# I2C_GPIOs_MIPI-CSI.net
KiCad netlist of a schematic drawn in Altium Designer
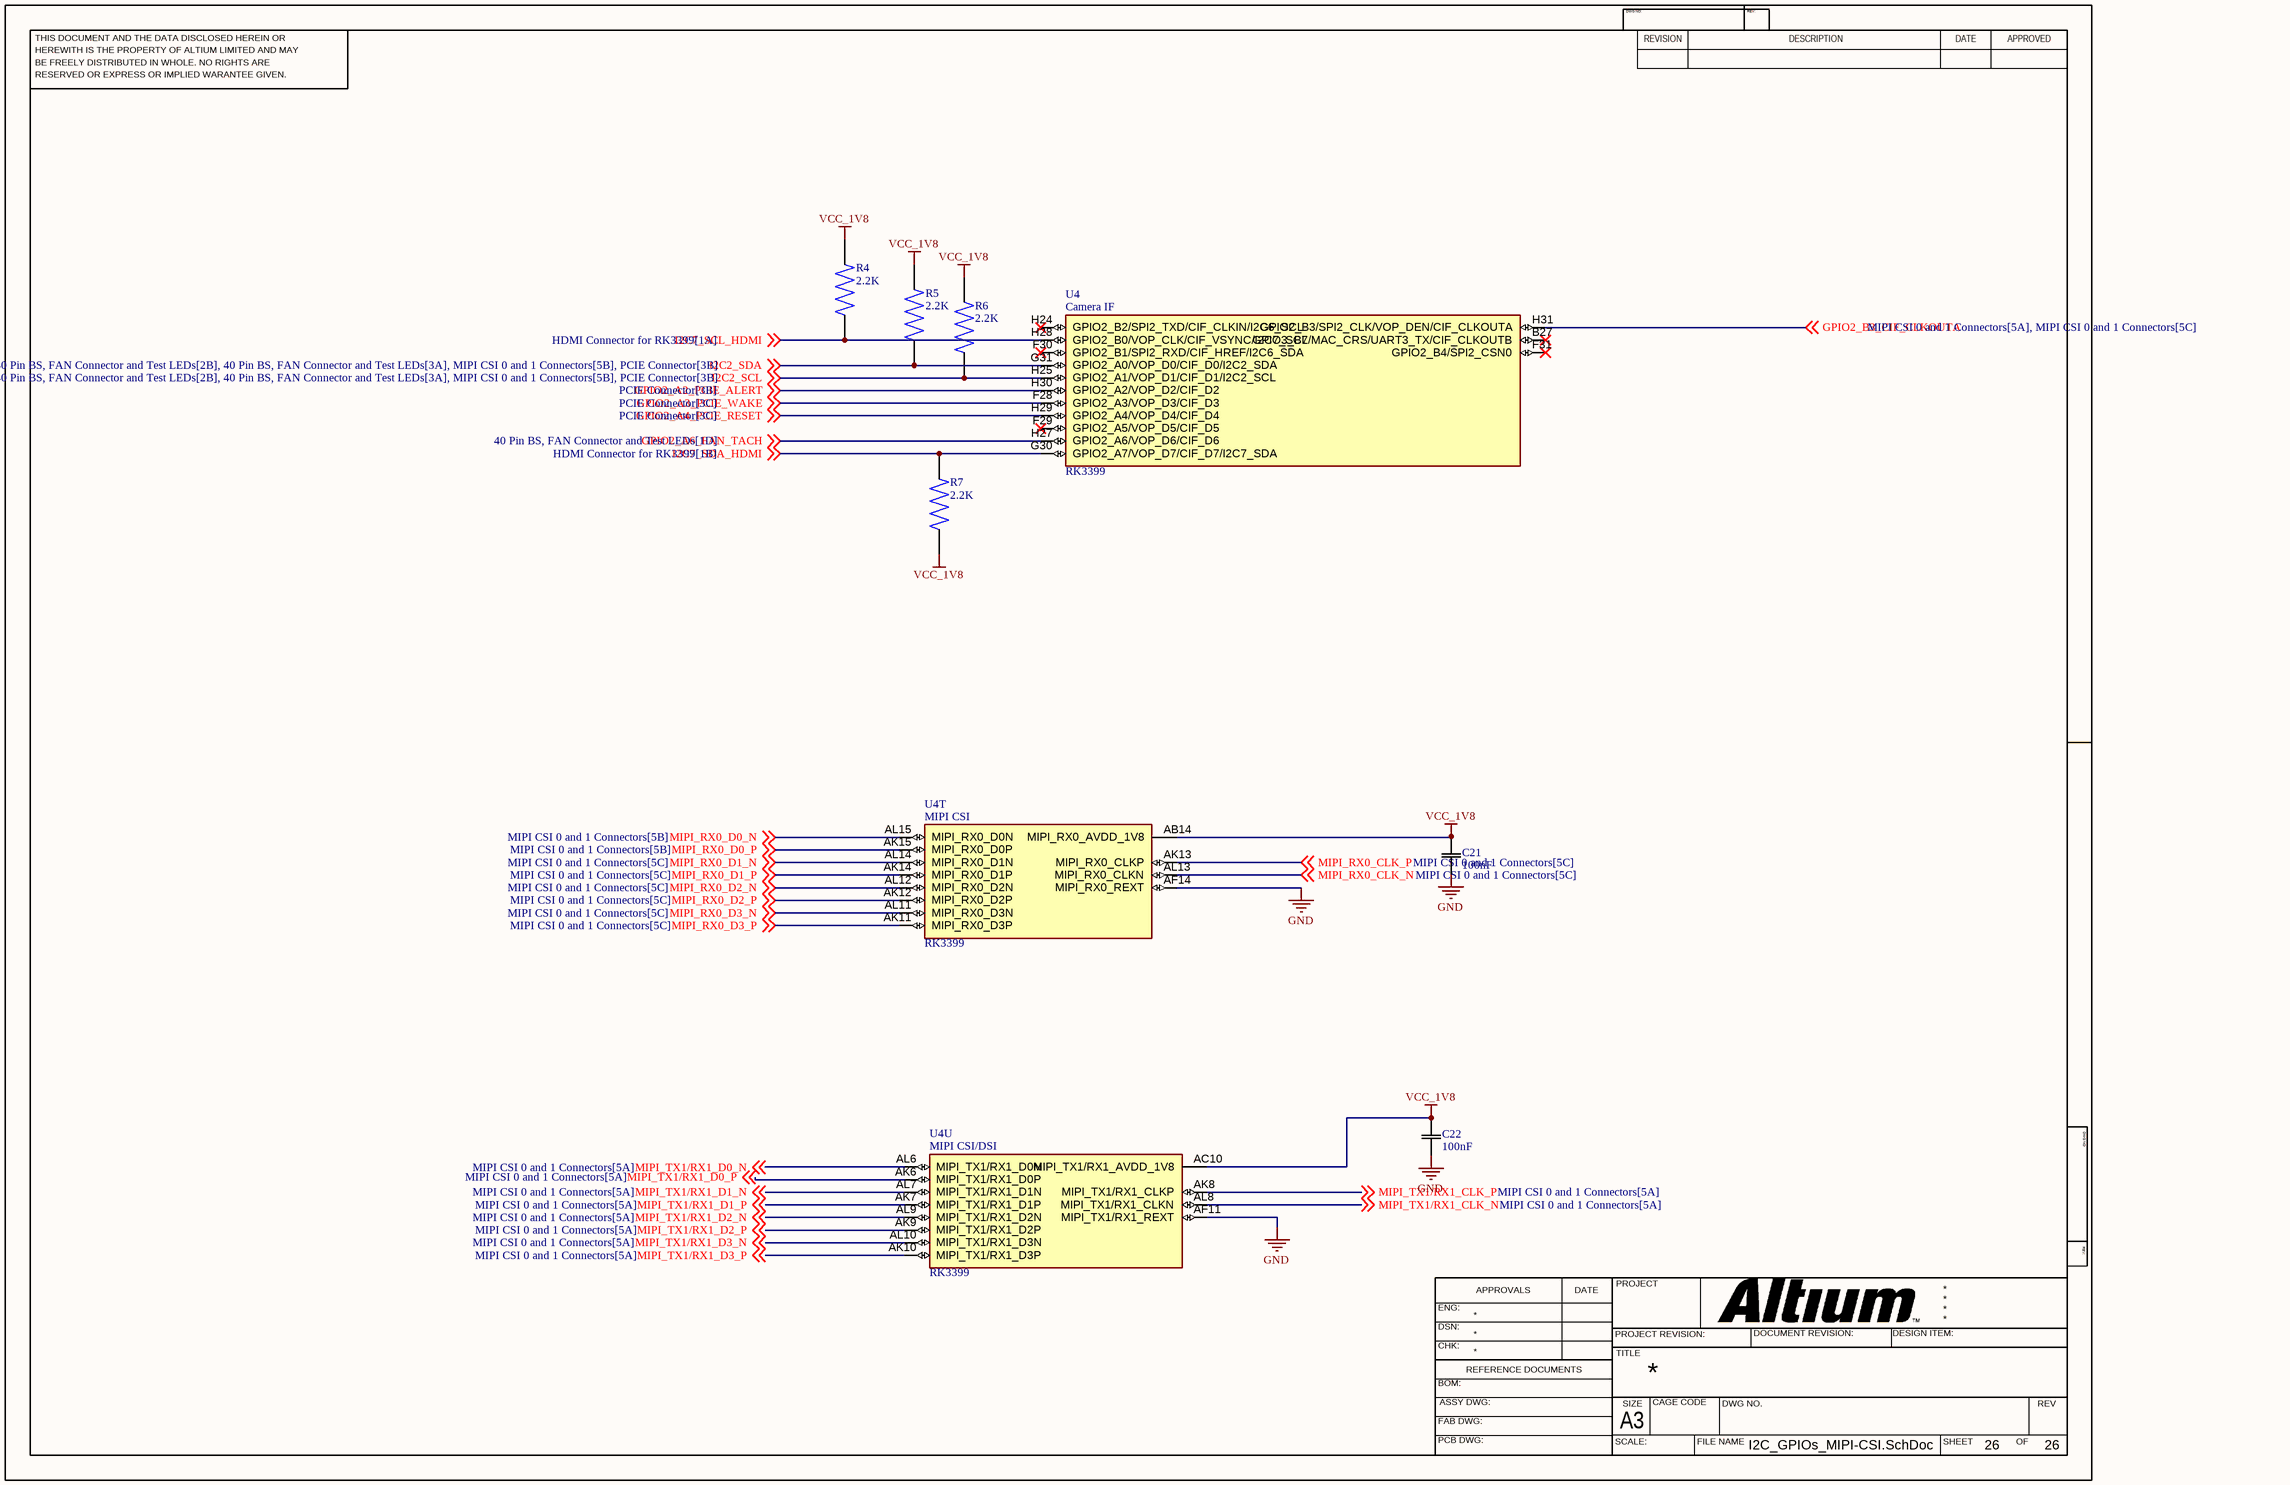
[diagram p0: I2C_GPIOs_MIPI-CSI.SchDoc]

(export (version "E")
  (design (tool "Eeschema 10.0.6"))
  (components
    (comp (ref "C21")
      (value "100nF")
      (footprint "CAP_1005_TDK")
      (description "Description")
      (fields
        (field (name "MANUFACTURER_PART_NUMBER") "C1005X7R1H104M050BB")
        (field (name "COPYRIGHT") "Copyright (C) 2025 Ultra Librarian. All rights reserved.")
      )
      (libsource (lib "C1005X7R1H104M050BB") (part "C1005X7R1H104M050BB"))
    )
    (comp (ref "C22")
      (value "100nF")
      (footprint "CAP_1005_TDK")
      (description "Description")
      (fields
        (field (name "MANUFACTURER_PART_NUMBER") "C1005X7R1H104M050BB")
        (field (name "COPYRIGHT") "Copyright (C) 2025 Ultra Librarian. All rights reserved.")
      )
      (libsource (lib "C1005X7R1H104M050BB") (part "C1005X7R1H104M050BB"))
    )
    (comp (ref "R4")
      (value "2.2K")
      (footprint "RES_ERA8APB222V")
      (fields (field (name "MP") "ERA8APB222V"))
      (libsource (lib "ERA8APB222V") (part "ERA8APB222V"))
    )
    (comp (ref "R5")
      (value "2.2K")
      (footprint "RES_ERA8APB222V")
      (fields (field (name "MP") "ERA8APB222V"))
      (libsource (lib "ERA8APB222V") (part "ERA8APB222V"))
    )
    (comp (ref "R6")
      (value "2.2K")
      (footprint "RES_ERA8APB222V")
      (fields (field (name "MP") "ERA8APB222V"))
      (libsource (lib "ERA8APB222V") (part "ERA8APB222V"))
    )
    (comp (ref "R7")
      (value "2.2K")
      (footprint "RES_ERA8APB222V")
      (fields (field (name "MP") "ERA8APB222V"))
      (libsource (lib "ERA8APB222V") (part "ERA8APB222V"))
    )
    (comp (ref "U4")
      (value "RK3399")
      (footprint "BGA828C65P31X31_2100X2100X161N")
      (description "RK3399 ROCK Pi 4 Model A 2GB - ARMÂ® CortexÂ®-A53, CortexÂ®-A72 MPU Embedded Evaluation Board")
      (fields (field (name "MF") "Rockchip"))
      (libsource (lib "Schlib1") (part "RK3399"))
    )
  )
  (nets
    (net (code "1") (name "GND") (class "Default")
      (node (ref "C21") (pin "1") (pinfunction "1_1") (pintype "passive"))
      (node (ref "C22") (pin "1") (pinfunction "1_1") (pintype "passive"))
      (node (ref "U4") (pin "AF11") (pinfunction "MIPI_TX1/RX1_REXT_AF11") (pintype "bidirectional"))
      (node (ref "U4") (pin "AF14") (pinfunction "MIPI_RX0_REXT_AF14") (pintype "bidirectional"))
    )
    (net (code "2") (name "GPIO2_A2_PCIE_ALERT") (class "Default")
      (node (ref "U4") (pin "H30") (pinfunction "GPIO2_A2/VOP_D2/CIF_D2_H30") (pintype "bidirectional"))
    )
    (net (code "3") (name "GPIO2_A3_PCIE_WAKE") (class "Default")
      (node (ref "U4") (pin "F28") (pinfunction "GPIO2_A3/VOP_D3/CIF_D3_F28") (pintype "bidirectional"))
    )
    (net (code "4") (name "GPIO2_A4_PCIE_RESET") (class "Default")
      (node (ref "U4") (pin "H29") (pinfunction "GPIO2_A4/VOP_D4/CIF_D4_H29") (pintype "bidirectional"))
    )
    (net (code "5") (name "GPIO2_A6_FAN_TACH") (class "Default")
      (node (ref "U4") (pin "H27") (pinfunction "GPIO2_A6/VOP_D6/CIF_D6_H27") (pintype "bidirectional"))
    )
    (net (code "6") (name "GPIO2_B3_CIF_CLKOUTA") (class "Default")
      (node (ref "U4") (pin "H31") (pinfunction "GPIO2_B3/SPI2_CLK/VOP_DEN/CIF_CLKOUTA_H31") (pintype "bidirectional"))
    )
    (net (code "7") (name "I2C2_SCL") (class "Default")
      (node (ref "R6") (pin "1") (pinfunction "1_1") (pintype "passive"))
      (node (ref "U4") (pin "H25") (pinfunction "GPIO2_A1/VOP_D1/CIF_D1/I2C2_SCL_H25") (pintype "bidirectional"))
    )
    (net (code "8") (name "I2C2_SDA") (class "Default")
      (node (ref "R5") (pin "1") (pinfunction "1_1") (pintype "passive"))
      (node (ref "U4") (pin "G31") (pinfunction "GPIO2_A0/VOP_D0/CIF_D0/I2C2_SDA_G31") (pintype "bidirectional"))
    )
    (net (code "9") (name "I2C7_SCL_HDMI") (class "Default")
      (node (ref "R4") (pin "1") (pinfunction "1_1") (pintype "passive"))
      (node (ref "U4") (pin "H28") (pinfunction "GPIO2_B0/VOP_CLK/CIF_VSYNC/I2C7_SCL_H28") (pintype "bidirectional"))
    )
    (net (code "10") (name "I2C7_SDA_HDMI") (class "Default")
      (node (ref "R7") (pin "2") (pinfunction "2_2") (pintype "passive"))
      (node (ref "U4") (pin "G30") (pinfunction "GPIO2_A7/VOP_D7/CIF_D7/I2C7_SDA_G30") (pintype "bidirectional"))
    )
    (net (code "11") (name "MIPI_RX0_CLK_N") (class "Default")
      (node (ref "U4") (pin "AL13") (pinfunction "MIPI_RX0_CLKN_AL13") (pintype "bidirectional"))
    )
    (net (code "12") (name "MIPI_RX0_CLK_P") (class "Default")
      (node (ref "U4") (pin "AK13") (pinfunction "MIPI_RX0_CLKP_AK13") (pintype "bidirectional"))
    )
    (net (code "13") (name "MIPI_RX0_D0_N") (class "Default")
      (node (ref "U4") (pin "AL15") (pinfunction "MIPI_RX0_D0N_AL15") (pintype "bidirectional"))
    )
    (net (code "14") (name "MIPI_RX0_D0_P") (class "Default")
      (node (ref "U4") (pin "AK15") (pinfunction "MIPI_RX0_D0P_AK15") (pintype "bidirectional"))
    )
    (net (code "15") (name "MIPI_RX0_D1_N") (class "Default")
      (node (ref "U4") (pin "AL14") (pinfunction "MIPI_RX0_D1N_AL14") (pintype "bidirectional"))
    )
    (net (code "16") (name "MIPI_RX0_D1_P") (class "Default")
      (node (ref "U4") (pin "AK14") (pinfunction "MIPI_RX0_D1P_AK14") (pintype "bidirectional"))
    )
    (net (code "17") (name "MIPI_RX0_D2_N") (class "Default")
      (node (ref "U4") (pin "AL12") (pinfunction "MIPI_RX0_D2N_AL12") (pintype "bidirectional"))
    )
    (net (code "18") (name "MIPI_RX0_D2_P") (class "Default")
      (node (ref "U4") (pin "AK12") (pinfunction "MIPI_RX0_D2P_AK12") (pintype "bidirectional"))
    )
    (net (code "19") (name "MIPI_RX0_D3_N") (class "Default")
      (node (ref "U4") (pin "AL11") (pinfunction "MIPI_RX0_D3N_AL11") (pintype "bidirectional"))
    )
    (net (code "20") (name "MIPI_RX0_D3_P") (class "Default")
      (node (ref "U4") (pin "AK11") (pinfunction "MIPI_RX0_D3P_AK11") (pintype "bidirectional"))
    )
    (net (code "21") (name "MIPI_TX1{slash}RX1_CLK_N") (class "Default")
      (node (ref "U4") (pin "AL8") (pinfunction "MIPI_TX1/RX1_CLKN_AL8") (pintype "bidirectional"))
    )
    (net (code "22") (name "MIPI_TX1{slash}RX1_CLK_P") (class "Default")
      (node (ref "U4") (pin "AK8") (pinfunction "MIPI_TX1/RX1_CLKP_AK8") (pintype "bidirectional"))
    )
    (net (code "23") (name "MIPI_TX1{slash}RX1_D0_N") (class "Default")
      (node (ref "U4") (pin "AL6") (pinfunction "MIPI_TX1/RX1_D0N_AL6") (pintype "bidirectional"))
    )
    (net (code "24") (name "MIPI_TX1{slash}RX1_D0_P") (class "Default")
      (node (ref "U4") (pin "AK6") (pinfunction "MIPI_TX1/RX1_D0P_AK6") (pintype "bidirectional"))
    )
    (net (code "25") (name "MIPI_TX1{slash}RX1_D1_N") (class "Default")
      (node (ref "U4") (pin "AL7") (pinfunction "MIPI_TX1/RX1_D1N_AL7") (pintype "bidirectional"))
    )
    (net (code "26") (name "MIPI_TX1{slash}RX1_D1_P") (class "Default")
      (node (ref "U4") (pin "AK7") (pinfunction "MIPI_TX1/RX1_D1P_AK7") (pintype "bidirectional"))
    )
    (net (code "27") (name "MIPI_TX1{slash}RX1_D2_N") (class "Default")
      (node (ref "U4") (pin "AL9") (pinfunction "MIPI_TX1/RX1_D2N_AL9") (pintype "bidirectional"))
    )
    (net (code "28") (name "MIPI_TX1{slash}RX1_D2_P") (class "Default")
      (node (ref "U4") (pin "AK9") (pinfunction "MIPI_TX1/RX1_D2P_AK9") (pintype "bidirectional"))
    )
    (net (code "29") (name "MIPI_TX1{slash}RX1_D3_N") (class "Default")
      (node (ref "U4") (pin "AL10") (pinfunction "MIPI_TX1/RX1_D3N_AL10") (pintype "bidirectional"))
    )
    (net (code "30") (name "MIPI_TX1{slash}RX1_D3_P") (class "Default")
      (node (ref "U4") (pin "AK10") (pinfunction "MIPI_TX1/RX1_D3P_AK10") (pintype "bidirectional"))
    )
    (net (code "31") (name "VCC_1V8") (class "Default")
      (node (ref "C21") (pin "2") (pinfunction "2_2") (pintype "passive"))
      (node (ref "C22") (pin "2") (pinfunction "2_2") (pintype "passive"))
      (node (ref "R4") (pin "2") (pinfunction "2_2") (pintype "passive"))
      (node (ref "R5") (pin "2") (pinfunction "2_2") (pintype "passive"))
      (node (ref "R6") (pin "2") (pinfunction "2_2") (pintype "passive"))
      (node (ref "R7") (pin "1") (pinfunction "1_1") (pintype "passive"))
      (node (ref "U4") (pin "AB14") (pinfunction "MIPI_RX0_AVDD_1V8_AB14") (pintype "power_in"))
      (node (ref "U4") (pin "AC10") (pinfunction "MIPI_TX1/RX1_AVDD_1V8_AC10") (pintype "power_in"))
    )
    (net (code "32") (name "unconnected-(U4AB-GPIO2_A5{slash}VOP_D5{slash}CIF_D5-PadF29)") (class "Default")
      (node (ref "U4") (pin "F29") (pinfunction "GPIO2_A5/VOP_D5/CIF_D5_F29") (pintype "bidirectional+no_connect"))
    )
    (net (code "33") (name "unconnected-(U4AB-GPIO2_B1{slash}SPI2_RXD{slash}CIF_HREF{slash}I2C6_SDA-PadF30)") (class "Default")
      (node (ref "U4") (pin "F30") (pinfunction "GPIO2_B1/SPI2_RXD/CIF_HREF/I2C6_SDA_F30") (pintype "bidirectional+no_connect"))
    )
    (net (code "34") (name "unconnected-(U4AB-GPIO2_B2{slash}SPI2_TXD{slash}CIF_CLKIN{slash}I2C6_SCL-PadH24)") (class "Default")
      (node (ref "U4") (pin "H24") (pinfunction "GPIO2_B2/SPI2_TXD/CIF_CLKIN/I2C6_SCL_H24") (pintype "bidirectional+no_connect"))
    )
    (net (code "35") (name "unconnected-(U4AB-GPIO2_B4{slash}SPI2_CSN0-PadF31)") (class "Default")
      (node (ref "U4") (pin "F31") (pinfunction "GPIO2_B4/SPI2_CSN0_F31") (pintype "bidirectional+no_connect"))
    )
    (net (code "36") (name "unconnected-(U4AB-GPIO3_B7{slash}MAC_CRS{slash}UART3_TX{slash}CIF_CLKOUTB-PadB27)") (class "Default")
      (node (ref "U4") (pin "B27") (pinfunction "GPIO3_B7/MAC_CRS/UART3_TX/CIF_CLKOUTB_B27") (pintype "bidirectional+no_connect"))
    )
  )
)
